# ltc3490-led-driver-12mm-mk-1.net
KiCad netlist of a schematic drawn in EAGLE
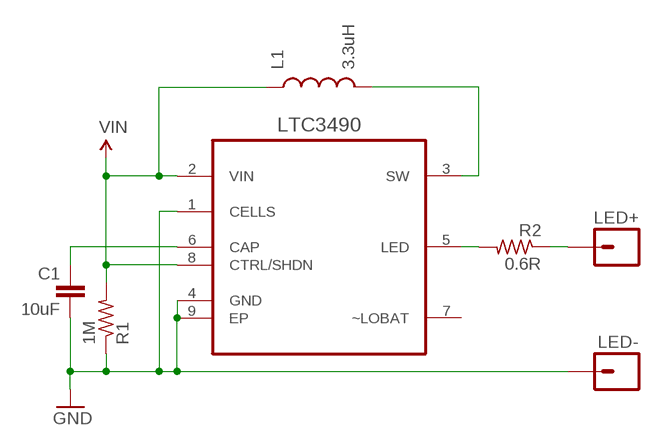
[diagram p0: schematic, sheet 1]

(export (version "E")
  (design (tool "Eeschema 10.0.6"))
  (components
    (comp (ref "C1")
      (value "10uF")
      (footprint "eagle-import:C0603")
      (libsource (lib "eagle-import") (part "CAPACITOR-CERAMICC0603"))
    )
    (comp (ref "L1")
      (value "3.3uH")
      (footprint "eagle-import:INDUCTOR_2X1.6MM")
      (libsource (lib "eagle-import") (part "INDUCTORIFSC-0806"))
    )
    (comp (ref "LED+")
      (value "M01PTH-1.2MM")
      (footprint "eagle-import:1X01-1.2MM")
      (libsource (lib "eagle-import") (part "M01PTH-1.2MM"))
    )
    (comp (ref "LED-")
      (value "M01PTH-1.2MM-NS")
      (footprint "eagle-import:1X01-1.2MM-NS")
      (libsource (lib "eagle-import") (part "M01PTH-1.2MM-NS"))
    )
    (comp (ref "LTC3490")
      (value "LTC3490EDDPBF")
      (footprint "eagle-import:DFN300X300X80-9N")
      (fields (field (name "MPN") "LTC3490EDD#PBF"))
      (libsource (lib "eagle-import") (part "LTC3490EDDPBF"))
    )
    (comp (ref "R1")
      (value "1M")
      (footprint "eagle-import:R0402")
      (libsource (lib "eagle-import") (part "RESISTORR0402"))
    )
    (comp (ref "R2")
      (value "0.6R")
      (footprint "eagle-import:R1206")
      (libsource (lib "eagle-import") (part "RESISTORR1206"))
    )
  )
  (nets
    (net (code "1") (name "GND") (class "Default")
      (node (ref "C1") (pin "2") (pinfunction "2_2") (pintype "passive"))
      (node (ref "LED-") (pin "P$1") (pinfunction "1_P$1") (pintype "passive"))
      (node (ref "LTC3490") (pin "1") (pinfunction "CELLS_1") (pintype "input"))
      (node (ref "LTC3490") (pin "4") (pinfunction "GND_4") (pintype "passive"))
      (node (ref "LTC3490") (pin "9") (pinfunction "EP_9") (pintype "passive"))
      (node (ref "R1") (pin "1") (pinfunction "1_1") (pintype "passive"))
    )
    (net (code "2") (name "Net-(L1-2)") (class "Default")
      (node (ref "L1") (pin "P$2") (pinfunction "2_P$2") (pintype "passive"))
      (node (ref "LTC3490") (pin "3") (pinfunction "SW_3") (pintype "input"))
    )
    (net (code "3") (name "Net-(LED+-1)") (class "Default")
      (node (ref "LED+") (pin "P$1") (pinfunction "1_P$1") (pintype "passive"))
      (node (ref "R2") (pin "1") (pinfunction "1_1") (pintype "passive"))
    )
    (net (code "4") (name "Net-(LTC3490-CAP)") (class "Default")
      (node (ref "C1") (pin "1") (pinfunction "1_1") (pintype "passive"))
      (node (ref "LTC3490") (pin "6") (pinfunction "CAP_6") (pintype "passive"))
    )
    (net (code "5") (name "Net-(LTC3490-LED)") (class "Default")
      (node (ref "LTC3490") (pin "5") (pinfunction "LED_5") (pintype "output"))
      (node (ref "R2") (pin "2") (pinfunction "2_2") (pintype "passive"))
    )
    (net (code "6") (name "VIN") (class "Default")
      (node (ref "L1") (pin "P$1") (pinfunction "1_P$1") (pintype "passive"))
      (node (ref "LTC3490") (pin "2") (pinfunction "VIN_2") (pintype "power_in"))
      (node (ref "LTC3490") (pin "8") (pinfunction "CTRL/SHDN_8") (pintype "input"))
      (node (ref "R1") (pin "2") (pinfunction "2_2") (pintype "passive"))
    )
    (net (code "7") (name "unconnected-(LTC3490-~{LOBAT}-Pad7)") (class "Default")
      (node (ref "LTC3490") (pin "7") (pinfunction "~{LOBAT}_7") (pintype "output"))
    )
  )
)
